# Ethernet_Connector.net
KiCad netlist of a schematic drawn in Altium Designer
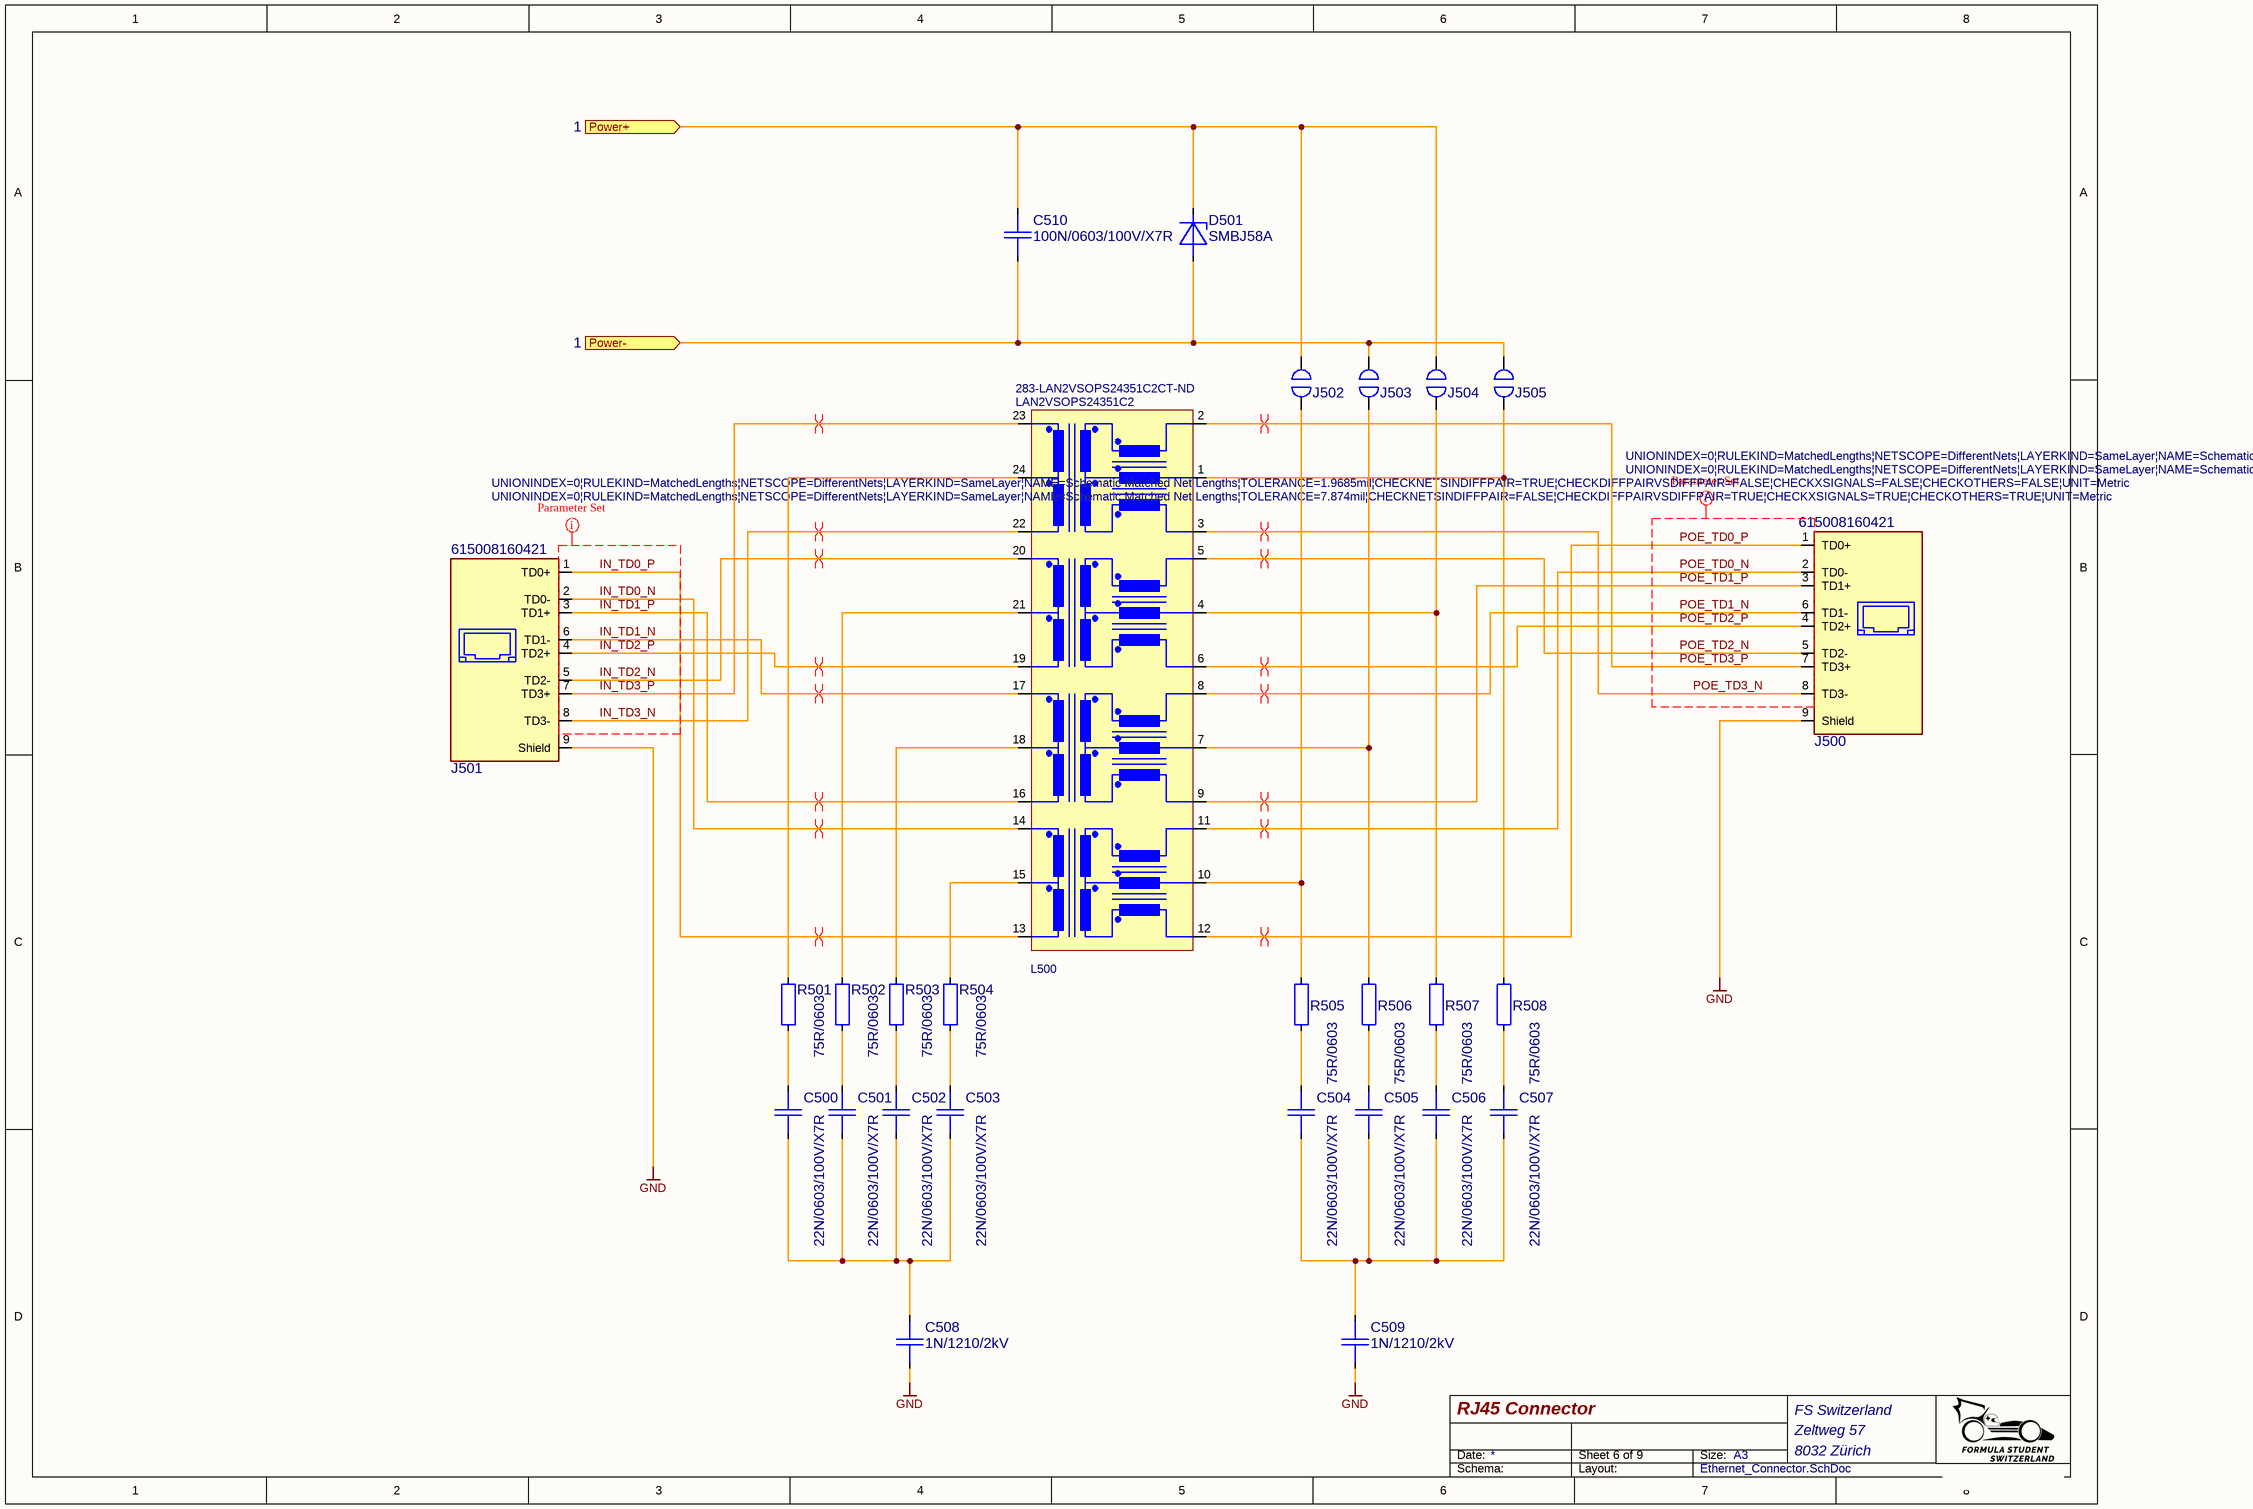
[diagram p0: Ethernet_Connector.SchDoc]

(export (version "E")
  (design (tool "Eeschema 10.0.6"))
  (components
    (comp (ref "C500")
      (value "22N/0603/100V/X7R")
      (footprint "CAP0603_X7R")
      (description "CAP SM 0603 22nF 100V X7R")
      (fields (field (name "MANUFACTURER") "GENERIC"))
      (libsource (lib "daniw_altium_lib") (part "C"))
    )
    (comp (ref "C501")
      (value "22N/0603/100V/X7R")
      (footprint "CAP0603_X7R")
      (description "CAP SM 0603 22nF 100V X7R")
      (fields (field (name "MANUFACTURER") "GENERIC"))
      (libsource (lib "daniw_altium_lib") (part "C"))
    )
    (comp (ref "C502")
      (value "22N/0603/100V/X7R")
      (footprint "CAP0603_X7R")
      (description "CAP SM 0603 22nF 100V X7R")
      (fields (field (name "MANUFACTURER") "GENERIC"))
      (libsource (lib "daniw_altium_lib") (part "C"))
    )
    (comp (ref "C503")
      (value "22N/0603/100V/X7R")
      (footprint "CAP0603_X7R")
      (description "CAP SM 0603 22nF 100V X7R")
      (fields (field (name "MANUFACTURER") "GENERIC"))
      (libsource (lib "daniw_altium_lib") (part "C"))
    )
    (comp (ref "C504")
      (value "22N/0603/100V/X7R")
      (footprint "CAP0603_X7R")
      (description "CAP SM 0603 22nF 100V X7R")
      (fields (field (name "MANUFACTURER") "GENERIC"))
      (libsource (lib "daniw_altium_lib") (part "C"))
    )
    (comp (ref "C505")
      (value "22N/0603/100V/X7R")
      (footprint "CAP0603_X7R")
      (description "CAP SM 0603 22nF 100V X7R")
      (fields (field (name "MANUFACTURER") "GENERIC"))
      (libsource (lib "daniw_altium_lib") (part "C"))
    )
    (comp (ref "C506")
      (value "22N/0603/100V/X7R")
      (footprint "CAP0603_X7R")
      (description "CAP SM 0603 22nF 100V X7R")
      (fields (field (name "MANUFACTURER") "GENERIC"))
      (libsource (lib "daniw_altium_lib") (part "C"))
    )
    (comp (ref "C507")
      (value "22N/0603/100V/X7R")
      (footprint "CAP0603_X7R")
      (description "CAP SM 0603 22nF 100V X7R")
      (fields (field (name "MANUFACTURER") "GENERIC"))
      (libsource (lib "daniw_altium_lib") (part "C"))
    )
    (comp (ref "C508")
      (value "1N/1210/2kV")
      (footprint "CAP1210_X7R")
      (description "CAP SM 1210 1nF 2kV")
      (fields (field (name "MANUFACTURER") "GENERIC"))
      (libsource (lib "daniw_altium_lib") (part "C"))
    )
    (comp (ref "C509")
      (value "1N/1210/2kV")
      (footprint "CAP1210_X7R")
      (description "CAP SM 1210 1nF 2kV")
      (fields (field (name "MANUFACTURER") "GENERIC"))
      (libsource (lib "daniw_altium_lib") (part "C"))
    )
    (comp (ref "C510")
      (value "100N/0603/100V/X7R")
      (footprint "CAP0603_X7R")
      (description "CAP SM 0603 100nF 100V X7R")
      (fields (field (name "MANUFACTURER") "GENERIC"))
      (libsource (lib "daniw_altium_lib") (part "C"))
    )
    (comp (ref "D501")
      (value "SMBJ58A")
      (footprint "DIOM5436X265")
      (description "TVS DIODE 58VWM 93.6VC DO214AA")
      (fields (field (name "MANUFACTURER") "Littelfuse Inc."))
      (libsource (lib "daniw_altium_lib") (part "D_Zener"))
    )
    (comp (ref "J500")
      (value "615008160421")
      (footprint "ETH_615008160421")
      (description "CONN MOD JACK 8P8C VERT SHIELDED")
      (fields (field (name "PART NUMBER") "ETH_THT_Vert_Schielded") (field (name "MANUFACTURER") "GENERIC"))
      (libsource (lib "") (part "RJ-45 ETH W/O LED_1"))
    )
    (comp (ref "J501")
      (value "615008160421")
      (footprint "ETH_615008160421")
      (description "CONN MOD JACK 8P8C VERT SHIELDED")
      (fields (field (name "PART NUMBER") "ETH_THT_Vert_Schielded") (field (name "MANUFACTURER") "GENERIC"))
      (libsource (lib "daniw_altium_lib") (part "RJ-45 ETH W/O LED"))
    )
    (comp (ref "J502")
      (value "Solder Jumper 2pin 0.2mm small")
      (footprint "Solder_Jumper_2pin_0.2mm_small")
      (description "Solder jumper with two pins with a spacing of 0.2mm")
      (fields
        (field (name "PART NUMBER") "Solder_Jumper_2pin_0.2mm_small")
        (field (name "MANUFACTURER") "NONE")
      )
      (libsource (lib "daniw_altium_lib") (part "SolderJumper_2"))
    )
    (comp (ref "J503")
      (value "Solder Jumper 2pin 0.2mm small")
      (footprint "Solder_Jumper_2pin_0.2mm_small")
      (description "Solder jumper with two pins with a spacing of 0.2mm")
      (fields
        (field (name "PART NUMBER") "Solder_Jumper_2pin_0.2mm_small")
        (field (name "MANUFACTURER") "NONE")
      )
      (libsource (lib "daniw_altium_lib") (part "SolderJumper_2"))
    )
    (comp (ref "J504")
      (value "Solder Jumper 2pin 0.2mm small")
      (footprint "Solder_Jumper_2pin_0.2mm_small")
      (description "Solder jumper with two pins with a spacing of 0.2mm")
      (fields
        (field (name "PART NUMBER") "Solder_Jumper_2pin_0.2mm_small")
        (field (name "MANUFACTURER") "NONE")
      )
      (libsource (lib "daniw_altium_lib") (part "SolderJumper_2"))
    )
    (comp (ref "J505")
      (value "Solder Jumper 2pin 0.2mm small")
      (footprint "Solder_Jumper_2pin_0.2mm_small")
      (description "Solder jumper with two pins with a spacing of 0.2mm")
      (fields
        (field (name "PART NUMBER") "Solder_Jumper_2pin_0.2mm_small")
        (field (name "MANUFACTURER") "NONE")
      )
      (libsource (lib "daniw_altium_lib") (part "SolderJumper_2"))
    )
    (comp (ref "L500")
      (value "LAN2VSOPS24351C2")
      (footprint "IND127P1600X620-24")
      (description "350µH LAN 1000 Base-T, Power over Ethernet (PoE) Pulswandler 1CT:1CT Oberflächenmontage")
      (fields
        (field (name "MANUFACTURER") "Eaton")
        (field (name "SUPPLIER PART NUMBER 1") "283-LAN2VSOPS24351C2CT-ND")
      )
      (libsource (lib "daniw_altium_lib") (part "Pulse_4Channel_CT"))
    )
    (comp (ref "R501")
      (value "75R/0603")
      (footprint "R0603-0.40-WW")
      (description "RES SM 0603 75R")
      (fields (field (name "MANUFACTURER") "GENERIC"))
      (libsource (lib "daniw_altium_lib") (part "R"))
    )
    (comp (ref "R502")
      (value "75R/0603")
      (footprint "R0603-0.40-WW")
      (description "RES SM 0603 75R")
      (fields (field (name "MANUFACTURER") "GENERIC"))
      (libsource (lib "daniw_altium_lib") (part "R"))
    )
    (comp (ref "R503")
      (value "75R/0603")
      (footprint "R0603-0.40-WW")
      (description "RES SM 0603 75R")
      (fields (field (name "MANUFACTURER") "GENERIC"))
      (libsource (lib "daniw_altium_lib") (part "R"))
    )
    (comp (ref "R504")
      (value "75R/0603")
      (footprint "R0603-0.40-WW")
      (description "RES SM 0603 75R")
      (fields (field (name "MANUFACTURER") "GENERIC"))
      (libsource (lib "daniw_altium_lib") (part "R"))
    )
    (comp (ref "R505")
      (value "75R/0603")
      (footprint "R0603-0.40-WW")
      (description "RES SM 0603 75R")
      (fields (field (name "MANUFACTURER") "GENERIC"))
      (libsource (lib "daniw_altium_lib") (part "R"))
    )
    (comp (ref "R506")
      (value "75R/0603")
      (footprint "R0603-0.40-WW")
      (description "RES SM 0603 75R")
      (fields (field (name "MANUFACTURER") "GENERIC"))
      (libsource (lib "daniw_altium_lib") (part "R"))
    )
    (comp (ref "R507")
      (value "75R/0603")
      (footprint "R0603-0.40-WW")
      (description "RES SM 0603 75R")
      (fields (field (name "MANUFACTURER") "GENERIC"))
      (libsource (lib "daniw_altium_lib") (part "R"))
    )
    (comp (ref "R508")
      (value "75R/0603")
      (footprint "R0603-0.40-WW")
      (description "RES SM 0603 75R")
      (fields (field (name "MANUFACTURER") "GENERIC"))
      (libsource (lib "daniw_altium_lib") (part "R"))
    )
  )
  (nets
    (net (code "1") (name "/IN_TD0_N") (class "Default")
      (node (ref "J501") (pin "2") (pinfunction "TD0-_2") (pintype "passive"))
      (node (ref "L500") (pin "14") (pintype "passive"))
    )
    (net (code "2") (name "/IN_TD0_P") (class "Default")
      (node (ref "J501") (pin "1") (pinfunction "TD0+_1") (pintype "passive"))
      (node (ref "L500") (pin "13") (pintype "passive"))
    )
    (net (code "3") (name "/IN_TD1_N") (class "Default")
      (node (ref "J501") (pin "6") (pinfunction "TD1-_6") (pintype "passive"))
      (node (ref "L500") (pin "17") (pintype "passive"))
    )
    (net (code "4") (name "/IN_TD1_P") (class "Default")
      (node (ref "J501") (pin "3") (pinfunction "TD1+_3") (pintype "passive"))
      (node (ref "L500") (pin "16") (pintype "passive"))
    )
    (net (code "5") (name "/IN_TD2_N") (class "Default")
      (node (ref "J501") (pin "5") (pinfunction "TD2-_5") (pintype "passive"))
      (node (ref "L500") (pin "20") (pintype "passive"))
    )
    (net (code "6") (name "/IN_TD2_P") (class "Default")
      (node (ref "J501") (pin "4") (pinfunction "TD2+_4") (pintype "passive"))
      (node (ref "L500") (pin "19") (pintype "passive"))
    )
    (net (code "7") (name "/IN_TD3_N") (class "Default")
      (node (ref "J501") (pin "8") (pinfunction "TD3-_8") (pintype "passive"))
      (node (ref "L500") (pin "22") (pintype "passive"))
    )
    (net (code "8") (name "/IN_TD3_P") (class "Default")
      (node (ref "J501") (pin "7") (pinfunction "TD3+_7") (pintype "passive"))
      (node (ref "L500") (pin "23") (pintype "passive"))
    )
    (net (code "9") (name "/POE_TD0_N") (class "Default")
      (node (ref "J500") (pin "2") (pinfunction "TD0-_2") (pintype "passive"))
      (node (ref "L500") (pin "11") (pintype "passive"))
    )
    (net (code "10") (name "/POE_TD0_P") (class "Default")
      (node (ref "J500") (pin "1") (pinfunction "TD0+_1") (pintype "passive"))
      (node (ref "L500") (pin "12") (pintype "passive"))
    )
    (net (code "11") (name "/POE_TD1_N") (class "Default")
      (node (ref "J500") (pin "6") (pinfunction "TD1-_6") (pintype "passive"))
      (node (ref "L500") (pin "8") (pintype "passive"))
    )
    (net (code "12") (name "/POE_TD1_P") (class "Default")
      (node (ref "J500") (pin "3") (pinfunction "TD1+_3") (pintype "passive"))
      (node (ref "L500") (pin "9") (pintype "passive"))
    )
    (net (code "13") (name "/POE_TD2_N") (class "Default")
      (node (ref "J500") (pin "5") (pinfunction "TD2-_5") (pintype "passive"))
      (node (ref "L500") (pin "5") (pintype "passive"))
    )
    (net (code "14") (name "/POE_TD2_P") (class "Default")
      (node (ref "J500") (pin "4") (pinfunction "TD2+_4") (pintype "passive"))
      (node (ref "L500") (pin "6") (pintype "passive"))
    )
    (net (code "15") (name "/POE_TD3_N") (class "Default")
      (node (ref "J500") (pin "8") (pinfunction "TD3-_8") (pintype "passive"))
      (node (ref "L500") (pin "3") (pintype "passive"))
    )
    (net (code "16") (name "/POE_TD3_P") (class "Default")
      (node (ref "J500") (pin "7") (pinfunction "TD3+_7") (pintype "passive"))
      (node (ref "L500") (pin "2") (pintype "passive"))
    )
    (net (code "17") (name "/Power+") (class "Default")
      (node (ref "C510") (pin "1") (pinfunction "1_1") (pintype "passive"))
      (node (ref "D501") (pin "1") (pinfunction "1_1") (pintype "passive"))
      (node (ref "J502") (pin "1") (pinfunction "1_1") (pintype "passive"))
      (node (ref "J504") (pin "1") (pinfunction "1_1") (pintype "passive"))
    )
    (net (code "18") (name "/Power-") (class "Default")
      (node (ref "C510") (pin "2") (pinfunction "2_2") (pintype "passive"))
      (node (ref "D501") (pin "2") (pinfunction "2_2") (pintype "passive"))
      (node (ref "J503") (pin "1") (pinfunction "1_1") (pintype "passive"))
      (node (ref "J505") (pin "1") (pinfunction "1_1") (pintype "passive"))
    )
    (net (code "19") (name "GND") (class "Default")
      (node (ref "C508") (pin "2") (pinfunction "2_2") (pintype "passive"))
      (node (ref "C509") (pin "2") (pinfunction "2_2") (pintype "passive"))
      (node (ref "J500") (pin "9") (pinfunction "Shield_9") (pintype "passive"))
      (node (ref "J501") (pin "9") (pinfunction "Shield_9") (pintype "passive"))
    )
    (net (code "20") (name "Net-(C500-Pad1)") (class "Default")
      (node (ref "C500") (pin "1") (pinfunction "1_1") (pintype "passive"))
      (node (ref "R501") (pin "2") (pinfunction "2_2") (pintype "passive"))
    )
    (net (code "21") (name "Net-(C500-Pad2)") (class "Default")
      (node (ref "C500") (pin "2") (pinfunction "2_2") (pintype "passive"))
      (node (ref "C501") (pin "2") (pinfunction "2_2") (pintype "passive"))
      (node (ref "C502") (pin "2") (pinfunction "2_2") (pintype "passive"))
      (node (ref "C503") (pin "2") (pinfunction "2_2") (pintype "passive"))
      (node (ref "C508") (pin "1") (pinfunction "1_1") (pintype "passive"))
    )
    (net (code "22") (name "Net-(C501-Pad1)") (class "Default")
      (node (ref "C501") (pin "1") (pinfunction "1_1") (pintype "passive"))
      (node (ref "R502") (pin "2") (pinfunction "2_2") (pintype "passive"))
    )
    (net (code "23") (name "Net-(C502-Pad1)") (class "Default")
      (node (ref "C502") (pin "1") (pinfunction "1_1") (pintype "passive"))
      (node (ref "R503") (pin "2") (pinfunction "2_2") (pintype "passive"))
    )
    (net (code "24") (name "Net-(C503-Pad1)") (class "Default")
      (node (ref "C503") (pin "1") (pinfunction "1_1") (pintype "passive"))
      (node (ref "R504") (pin "2") (pinfunction "2_2") (pintype "passive"))
    )
    (net (code "25") (name "Net-(C504-Pad1)") (class "Default")
      (node (ref "C504") (pin "1") (pinfunction "1_1") (pintype "passive"))
      (node (ref "R505") (pin "2") (pinfunction "2_2") (pintype "passive"))
    )
    (net (code "26") (name "Net-(C504-Pad2)") (class "Default")
      (node (ref "C504") (pin "2") (pinfunction "2_2") (pintype "passive"))
      (node (ref "C505") (pin "2") (pinfunction "2_2") (pintype "passive"))
      (node (ref "C506") (pin "2") (pinfunction "2_2") (pintype "passive"))
      (node (ref "C507") (pin "2") (pinfunction "2_2") (pintype "passive"))
      (node (ref "C509") (pin "1") (pinfunction "1_1") (pintype "passive"))
    )
    (net (code "27") (name "Net-(C505-Pad1)") (class "Default")
      (node (ref "C505") (pin "1") (pinfunction "1_1") (pintype "passive"))
      (node (ref "R506") (pin "2") (pinfunction "2_2") (pintype "passive"))
    )
    (net (code "28") (name "Net-(C506-Pad1)") (class "Default")
      (node (ref "C506") (pin "1") (pinfunction "1_1") (pintype "passive"))
      (node (ref "R507") (pin "2") (pinfunction "2_2") (pintype "passive"))
    )
    (net (code "29") (name "Net-(C507-Pad1)") (class "Default")
      (node (ref "C507") (pin "1") (pinfunction "1_1") (pintype "passive"))
      (node (ref "R508") (pin "2") (pinfunction "2_2") (pintype "passive"))
    )
    (net (code "30") (name "Net-(J502-Pad2)") (class "Default")
      (node (ref "J502") (pin "2") (pinfunction "2_2") (pintype "passive"))
      (node (ref "L500") (pin "10") (pintype "passive"))
      (node (ref "R505") (pin "1") (pinfunction "1_1") (pintype "passive"))
    )
    (net (code "31") (name "Net-(J503-Pad2)") (class "Default")
      (node (ref "J503") (pin "2") (pinfunction "2_2") (pintype "passive"))
      (node (ref "L500") (pin "7") (pintype "passive"))
      (node (ref "R506") (pin "1") (pinfunction "1_1") (pintype "passive"))
    )
    (net (code "32") (name "Net-(J504-Pad2)") (class "Default")
      (node (ref "J504") (pin "2") (pinfunction "2_2") (pintype "passive"))
      (node (ref "L500") (pin "4") (pintype "passive"))
      (node (ref "R507") (pin "1") (pinfunction "1_1") (pintype "passive"))
    )
    (net (code "33") (name "Net-(J505-Pad2)") (class "Default")
      (node (ref "J505") (pin "2") (pinfunction "2_2") (pintype "passive"))
      (node (ref "L500") (pin "1") (pintype "passive"))
      (node (ref "R508") (pin "1") (pinfunction "1_1") (pintype "passive"))
    )
    (net (code "34") (name "Net-(L500-Pad15)") (class "Default")
      (node (ref "L500") (pin "15") (pintype "passive"))
      (node (ref "R504") (pin "1") (pinfunction "1_1") (pintype "passive"))
    )
    (net (code "35") (name "Net-(L500-Pad18)") (class "Default")
      (node (ref "L500") (pin "18") (pintype "passive"))
      (node (ref "R503") (pin "1") (pinfunction "1_1") (pintype "passive"))
    )
    (net (code "36") (name "Net-(L500-Pad21)") (class "Default")
      (node (ref "L500") (pin "21") (pintype "passive"))
      (node (ref "R502") (pin "1") (pinfunction "1_1") (pintype "passive"))
    )
    (net (code "37") (name "Net-(L500-Pad24)") (class "Default")
      (node (ref "L500") (pin "24") (pintype "passive"))
      (node (ref "R501") (pin "1") (pinfunction "1_1") (pintype "passive"))
    )
  )
)
